# reefpi_pico_pi.net
KiCad netlist of a schematic drawn in Altium Designer
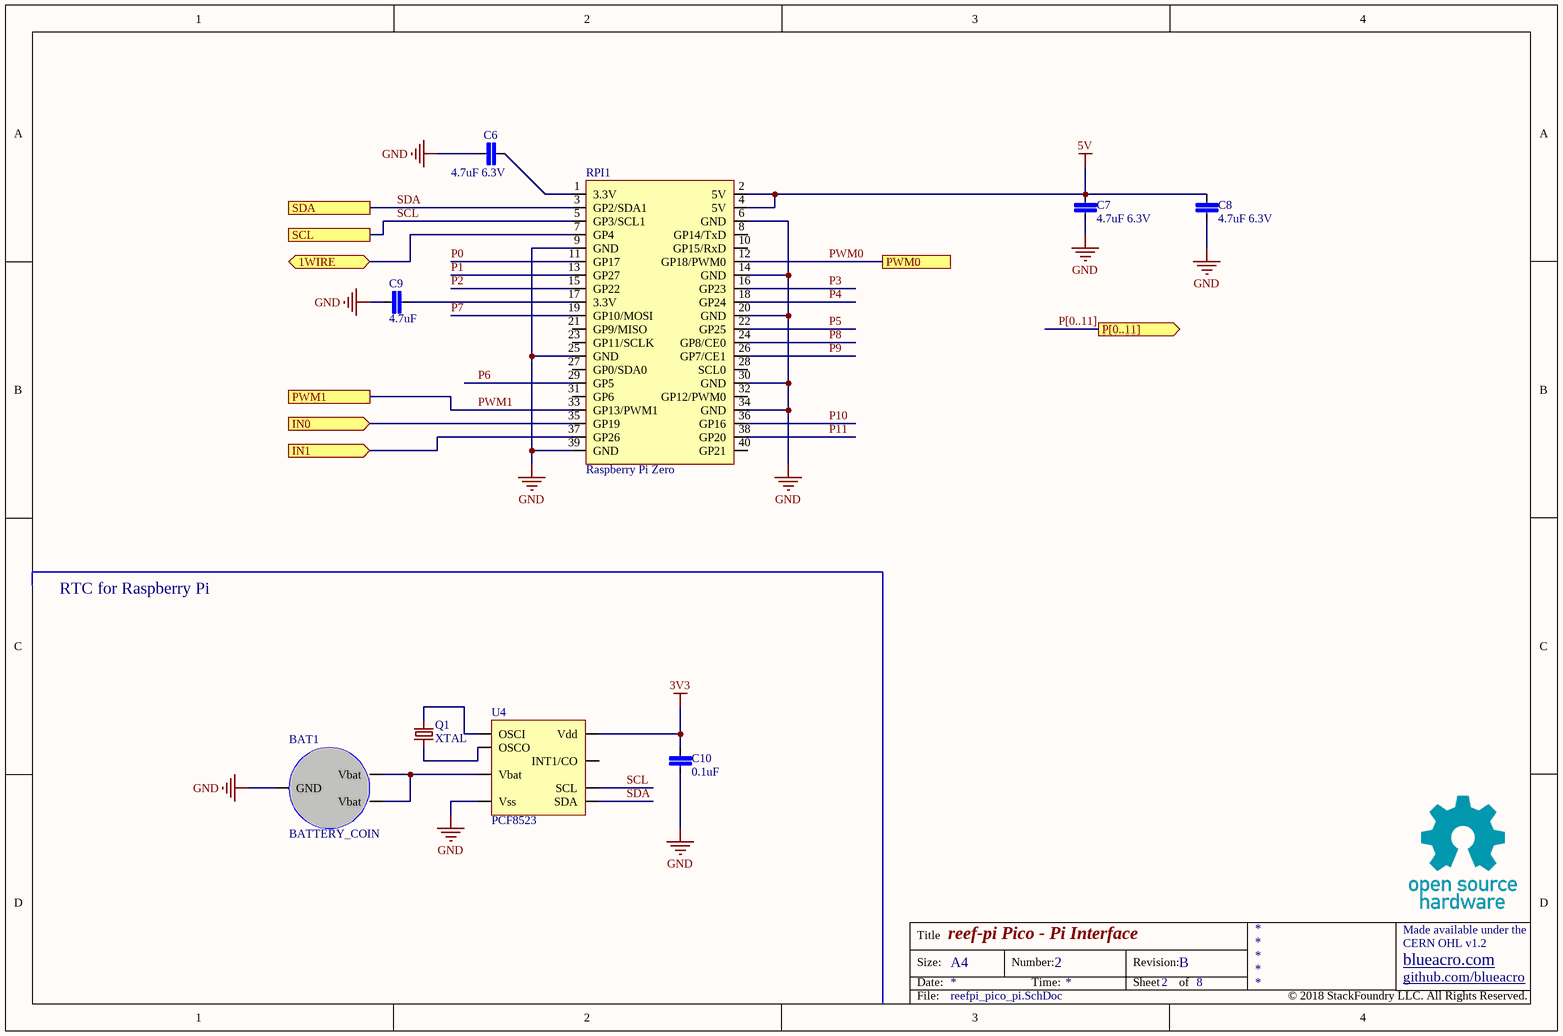
[diagram p0: reefpi_pico_pi.SchDoc]

(export (version "E")
  (design (tool "Eeschema 10.0.6"))
  (components
    (comp (ref "BAT1")
      (value "BATTERY_COIN")
      (footprint "BK-885-1216")
      (libsource (lib "connectors") (part "BATTERY_COIN"))
    )
    (comp (ref "C6") (value "4.7uF 6.3V") (footprint "C0603") (libsource (lib "") (part "C-EU_1")))
    (comp (ref "C7") (value "4.7uF 6.3V") (footprint "C0603") (libsource (lib "rcl") (part "C-EU")))
    (comp (ref "C8") (value "4.7uF 6.3V") (footprint "C0603") (libsource (lib "rcl") (part "C-EU")))
    (comp (ref "C9") (value "4.7uF") (footprint "C0603") (libsource (lib "") (part "C-EU_1")))
    (comp (ref "C10") (value "0.1uF") (footprint "C0603") (libsource (lib "rcl") (part "C-EU")))
    (comp (ref "Q1")
      (value "XTAL")
      (footprint "CRYSTAL-32KHZ-SMD")
      (libsource (lib "general") (part "CRYSTAL32-SMD"))
    )
    (comp (ref "RPI1")
      (value "Raspberry Pi Zero")
      (footprint "RPI_ZERO_W - FD")
      (libsource (lib "rpi") (part "RPI Zero"))
    )
    (comp (ref "U4") (value "PCF8523") (footprint "SO-8") (libsource (lib "general") (part "PCF8523")))
  )
  (nets
    (net (code "1") (name "/1WIRE") (class "Default")
      (node (ref "RPI1") (pin "7") (pinfunction "GP4_7") (pintype "passive"))
    )
    (net (code "2") (name "/IN0") (class "Default")
      (node (ref "RPI1") (pin "35") (pinfunction "GP19_35") (pintype "passive"))
    )
    (net (code "3") (name "/IN1") (class "Default")
      (node (ref "RPI1") (pin "37") (pinfunction "GP26_37") (pintype "passive"))
    )
    (net (code "4") (name "/P0") (class "Default")
      (node (ref "RPI1") (pin "11") (pinfunction "GP17_11") (pintype "passive"))
    )
    (net (code "5") (name "/P1") (class "Default")
      (node (ref "RPI1") (pin "13") (pinfunction "GP27_13") (pintype "passive"))
    )
    (net (code "6") (name "/P2") (class "Default")
      (node (ref "RPI1") (pin "15") (pinfunction "GP22_15") (pintype "passive"))
    )
    (net (code "7") (name "/P3") (class "Default")
      (node (ref "RPI1") (pin "16") (pinfunction "GP23_16") (pintype "passive"))
    )
    (net (code "8") (name "/P4") (class "Default")
      (node (ref "RPI1") (pin "18") (pinfunction "GP24_18") (pintype "passive"))
    )
    (net (code "9") (name "/P5") (class "Default")
      (node (ref "RPI1") (pin "22") (pinfunction "GP25_22") (pintype "passive"))
    )
    (net (code "10") (name "/P6") (class "Default")
      (node (ref "RPI1") (pin "29") (pinfunction "GP5_29") (pintype "passive"))
    )
    (net (code "11") (name "/P7") (class "Default")
      (node (ref "RPI1") (pin "19") (pinfunction "GP10/MOSI_19") (pintype "passive"))
    )
    (net (code "12") (name "/P8") (class "Default")
      (node (ref "RPI1") (pin "24") (pinfunction "GP8/CE0_24") (pintype "passive"))
    )
    (net (code "13") (name "/P9") (class "Default")
      (node (ref "RPI1") (pin "26") (pinfunction "GP7/CE1_26") (pintype "passive"))
    )
    (net (code "14") (name "/P10") (class "Default")
      (node (ref "RPI1") (pin "36") (pinfunction "GP16_36") (pintype "passive"))
    )
    (net (code "15") (name "/P11") (class "Default")
      (node (ref "RPI1") (pin "38") (pinfunction "GP20_38") (pintype "passive"))
    )
    (net (code "16") (name "/PWM0") (class "Default")
      (node (ref "RPI1") (pin "12") (pinfunction "GP18/PWM0_12") (pintype "passive"))
    )
    (net (code "17") (name "/PWM1") (class "Default")
      (node (ref "RPI1") (pin "33") (pinfunction "GP13/PWM1_33") (pintype "passive"))
    )
    (net (code "19") (name "/SCL") (class "Default")
      (node (ref "RPI1") (pin "5") (pinfunction "GP3/SCL1_5") (pintype "passive"))
      (node (ref "U4") (pin "6") (pinfunction "SCL_6") (pintype "passive"))
    )
    (net (code "20") (name "/SDA") (class "Default")
      (node (ref "RPI1") (pin "3") (pinfunction "GP2/SDA1_3") (pintype "passive"))
      (node (ref "U4") (pin "5") (pinfunction "SDA_5") (pintype "passive"))
    )
    (net (code "21") (name "3V3") (class "Default")
      (node (ref "C10") (pin "1") (pinfunction "1_1") (pintype "passive"))
      (node (ref "U4") (pin "8") (pinfunction "Vdd_8") (pintype "passive"))
    )
    (net (code "22") (name "5V") (class "Default")
      (node (ref "C7") (pin "1") (pinfunction "1_1") (pintype "passive"))
      (node (ref "C8") (pin "1") (pinfunction "1_1") (pintype "passive"))
      (node (ref "RPI1") (pin "2") (pinfunction "5V_2") (pintype "passive"))
      (node (ref "RPI1") (pin "4") (pinfunction "5V_4") (pintype "passive"))
    )
    (net (code "23") (name "GND") (class "Default")
      (node (ref "BAT1") (pin "GND") (pinfunction "GND_GND") (pintype "passive"))
      (node (ref "C10") (pin "2") (pinfunction "2_2") (pintype "passive"))
      (node (ref "C6") (pin "1") (pinfunction "1_1") (pintype "passive"))
      (node (ref "C7") (pin "2") (pinfunction "2_2") (pintype "passive"))
      (node (ref "C8") (pin "2") (pinfunction "2_2") (pintype "passive"))
      (node (ref "C9") (pin "1") (pinfunction "1_1") (pintype "passive"))
      (node (ref "RPI1") (pin "14") (pinfunction "GND_14") (pintype "passive"))
      (node (ref "RPI1") (pin "20") (pinfunction "GND_20") (pintype "passive"))
      (node (ref "RPI1") (pin "25") (pinfunction "GND_25") (pintype "passive"))
      (node (ref "RPI1") (pin "30") (pinfunction "GND_30") (pintype "passive"))
      (node (ref "RPI1") (pin "34") (pinfunction "GND_34") (pintype "passive"))
      (node (ref "RPI1") (pin "39") (pinfunction "GND_39") (pintype "passive"))
      (node (ref "RPI1") (pin "6") (pinfunction "GND_6") (pintype "passive"))
      (node (ref "RPI1") (pin "9") (pinfunction "GND_9") (pintype "passive"))
      (node (ref "U4") (pin "4") (pinfunction "Vss_4") (pintype "passive"))
    )
    (net (code "24") (name "Net-(C6-Pad2)") (class "Default")
      (node (ref "C6") (pin "2") (pinfunction "2_2") (pintype "passive"))
      (node (ref "RPI1") (pin "1") (pinfunction "3.3V_1") (pintype "passive"))
    )
    (net (code "25") (name "Net-(C9-Pad2)") (class "Default")
      (node (ref "C9") (pin "2") (pinfunction "2_2") (pintype "passive"))
      (node (ref "RPI1") (pin "17") (pinfunction "3.3V_17") (pintype "passive"))
    )
    (net (code "26") (name "Net-(Q1-1)") (class "Default")
      (node (ref "Q1") (pin "X1") (pinfunction "1_X1") (pintype "passive"))
      (node (ref "U4") (pin "2") (pinfunction "OSCO_2") (pintype "passive"))
    )
    (net (code "27") (name "Net-(Q1-2)") (class "Default")
      (node (ref "Q1") (pin "X2") (pinfunction "2_X2") (pintype "passive"))
      (node (ref "U4") (pin "1") (pinfunction "OSCI_1") (pintype "passive"))
    )
    (net (code "28") (name "Net-(U4-Vbat)") (class "Default")
      (node (ref "BAT1") (pin "VBAT1") (pinfunction "Vbat_VBAT1") (pintype "passive"))
      (node (ref "BAT1") (pin "VBAT2") (pinfunction "Vbat_VBAT2") (pintype "passive"))
      (node (ref "U4") (pin "3") (pinfunction "Vbat_3") (pintype "passive"))
    )
    (net (code "29") (name "unconnected-(RPI1-GP0{slash}SDA0-Pad27)") (class "Default")
      (node (ref "RPI1") (pin "27") (pinfunction "GP0/SDA0_27") (pintype "passive"))
    )
    (net (code "30") (name "unconnected-(RPI1-GP6-Pad31)") (class "Default")
      (node (ref "RPI1") (pin "31") (pinfunction "GP6_31") (pintype "passive"))
    )
    (net (code "31") (name "unconnected-(RPI1-GP9{slash}MISO-Pad21)") (class "Default")
      (node (ref "RPI1") (pin "21") (pinfunction "GP9/MISO_21") (pintype "passive"))
    )
    (net (code "32") (name "unconnected-(RPI1-GP11{slash}SCLK-Pad23)") (class "Default")
      (node (ref "RPI1") (pin "23") (pinfunction "GP11/SCLK_23") (pintype "passive"))
    )
    (net (code "33") (name "unconnected-(RPI1-GP12{slash}PWM0-Pad32)") (class "Default")
      (node (ref "RPI1") (pin "32") (pinfunction "GP12/PWM0_32") (pintype "passive"))
    )
    (net (code "34") (name "unconnected-(RPI1-GP14{slash}TxD-Pad8)") (class "Default")
      (node (ref "RPI1") (pin "8") (pinfunction "GP14/TxD_8") (pintype "passive"))
    )
    (net (code "35") (name "unconnected-(RPI1-GP15{slash}RxD-Pad10)") (class "Default")
      (node (ref "RPI1") (pin "10") (pinfunction "GP15/RxD_10") (pintype "passive"))
    )
    (net (code "36") (name "unconnected-(RPI1-GP21-Pad40)") (class "Default")
      (node (ref "RPI1") (pin "40") (pinfunction "GP21_40") (pintype "passive"))
    )
    (net (code "37") (name "unconnected-(RPI1-SCL0-Pad28)") (class "Default")
      (node (ref "RPI1") (pin "28") (pinfunction "SCL0_28") (pintype "passive"))
    )
    (net (code "38") (name "unconnected-(U4-INT1{slash}CO-Pad7)") (class "Default")
      (node (ref "U4") (pin "7") (pinfunction "INT1/CO_7") (pintype "passive"))
    )
  )
)
